# schematic.net
KiCad netlist of a schematic drawn in EasyEDA
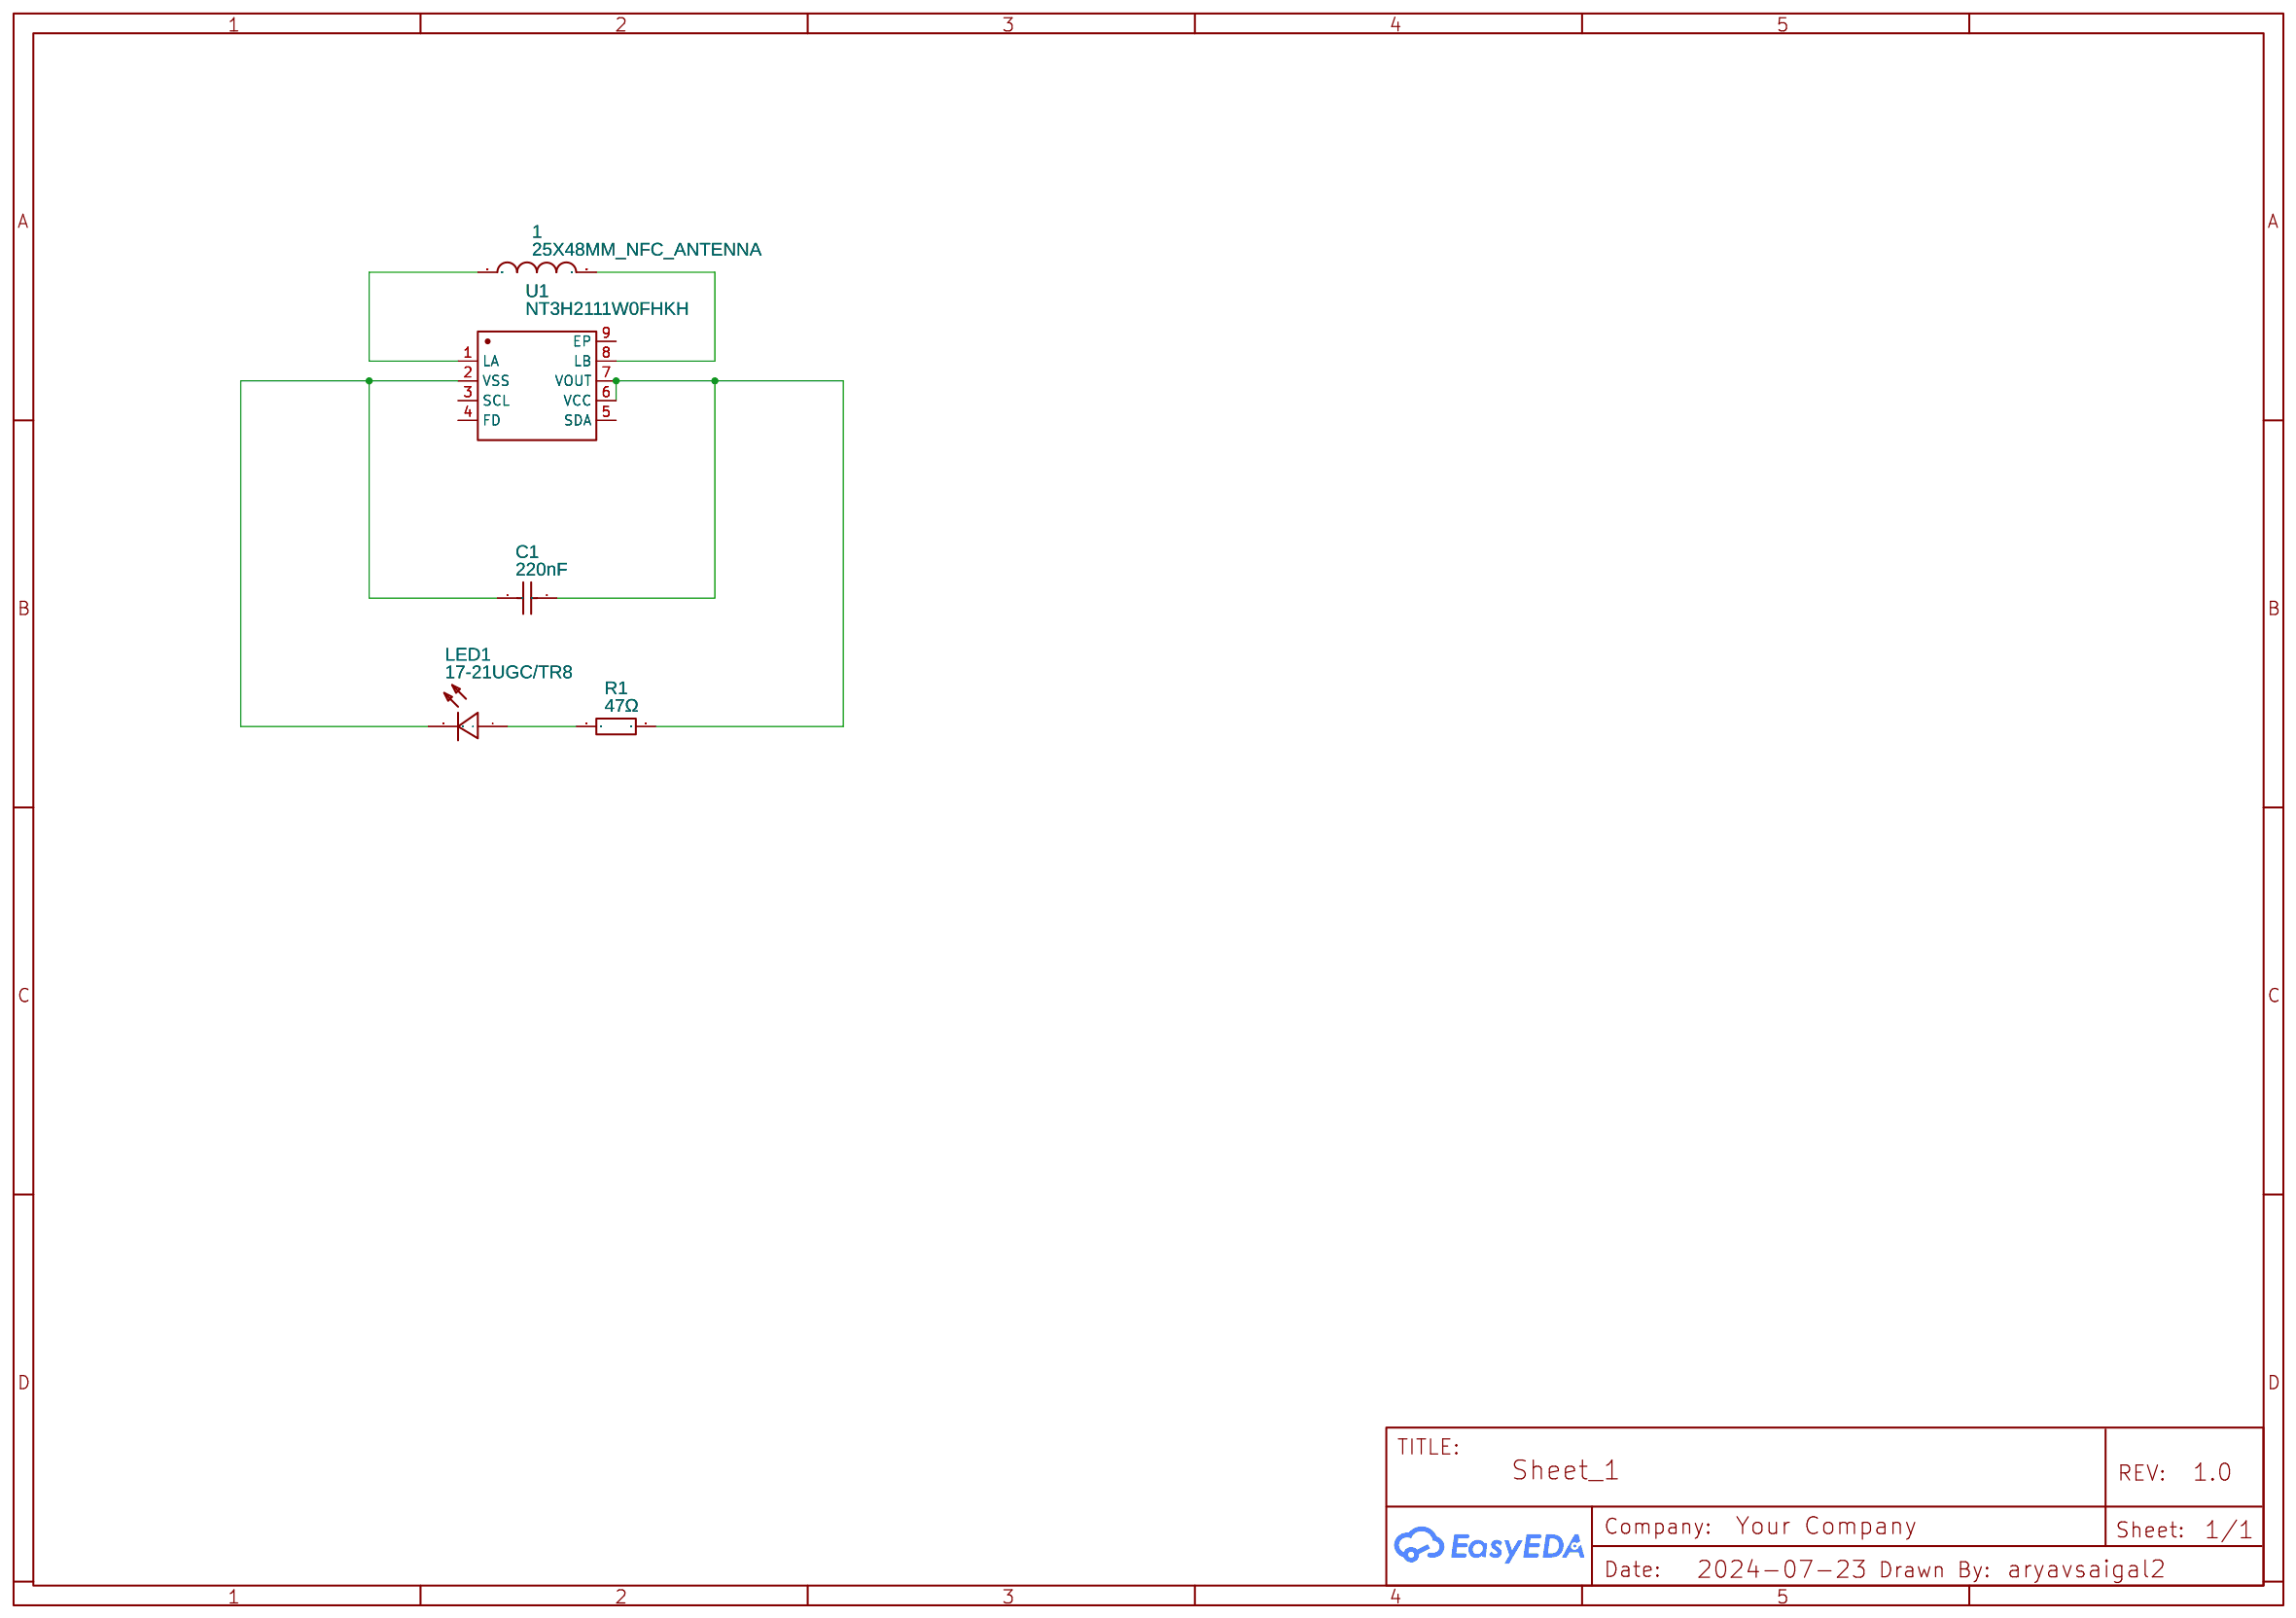
[diagram p0: schematic sheet]

(export (version "E")
  (design (tool "Eeschema 10.0.6"))
  (components
    (comp (ref "1") (value "25X48MM_NFC_ANTENNA") (libsource (lib "") (part "25X48MM_NFC_ANTENNA")))
    (comp (ref "C1")
      (value "220nF")
      (fields
        (field (name "Manufacturer Part") "CL10B224KA8NNNC")
        (field (name "Manufacturer") "SAMSUNG(三星)")
      )
      (libsource (lib "") (part "CL10B224KA8NNNC"))
    )
    (comp (ref "LED1")
      (value "17-21UGC/TR8")
      (fields (field (name "Manufacturer") "EVERLIGHT(亿光)"))
      (libsource (lib "") (part "17-21UGC/TR8"))
    )
    (comp (ref "R1")
      (value "47Ω")
      (fields
        (field (name "Manufacturer Part") "0603WAF470JT5E")
        (field (name "Manufacturer") "UNI-ROYAL(厚声)")
      )
      (libsource (lib "") (part "0603WAF470JT5E"))
    )
    (comp (ref "U1")
      (value "NT3H2111W0FHKH")
      (fields (field (name "Manufacturer") "NXP(恩智浦)"))
      (libsource (lib "") (part "NT3H2111W0FHKH"))
    )
  )
  (nets
    (net (code "1") (name "Net-(LED1-A)") (class "Default")
      (node (ref "LED1") (pin "1") (pinfunction "A_1") (pintype "unspecified"))
      (node (ref "R1") (pin "1") (pinfunction "1_1") (pintype "input"))
    )
    (net (code "2") (name "Net-(LED1-K)") (class "Default")
      (node (ref "C1") (pin "1") (pinfunction "1_1") (pintype "input"))
      (node (ref "LED1") (pin "2") (pinfunction "K_2") (pintype "unspecified"))
      (node (ref "U1") (pin "2") (pinfunction "VSS_2") (pintype "unspecified"))
    )
    (net (code "3") (name "Net-(U1-LA)") (class "Default")
      (node (ref "1") (pin "P$1") (pinfunction "P$1_P$1") (pintype "bidirectional"))
      (node (ref "U1") (pin "1") (pinfunction "LA_1") (pintype "unspecified"))
    )
    (net (code "4") (name "Net-(U1-LB)") (class "Default")
      (node (ref "1") (pin "P$2") (pinfunction "P$2_P$2") (pintype "bidirectional"))
      (node (ref "U1") (pin "8") (pinfunction "LB_8") (pintype "unspecified"))
    )
    (net (code "5") (name "Net-(U1-VCC)") (class "Default")
      (node (ref "C1") (pin "2") (pinfunction "2_2") (pintype "input"))
      (node (ref "R1") (pin "2") (pinfunction "2_2") (pintype "input"))
      (node (ref "U1") (pin "6") (pinfunction "VCC_6") (pintype "unspecified"))
      (node (ref "U1") (pin "7") (pinfunction "VOUT_7") (pintype "unspecified"))
    )
    (net (code "6") (name "unconnected-(U1-EP-Pad9)") (class "Default")
      (node (ref "U1") (pin "9") (pinfunction "EP_9") (pintype "unspecified"))
    )
    (net (code "7") (name "unconnected-(U1-FD-Pad4)") (class "Default")
      (node (ref "U1") (pin "4") (pinfunction "FD_4") (pintype "unspecified"))
    )
    (net (code "8") (name "unconnected-(U1-SCL-Pad3)") (class "Default")
      (node (ref "U1") (pin "3") (pinfunction "SCL_3") (pintype "unspecified"))
    )
    (net (code "9") (name "unconnected-(U1-SDA-Pad5)") (class "Default")
      (node (ref "U1") (pin "5") (pinfunction "SDA_5") (pintype "unspecified"))
    )
  )
)
